# rs485.net
KiCad netlist of a schematic drawn in Altium Designer
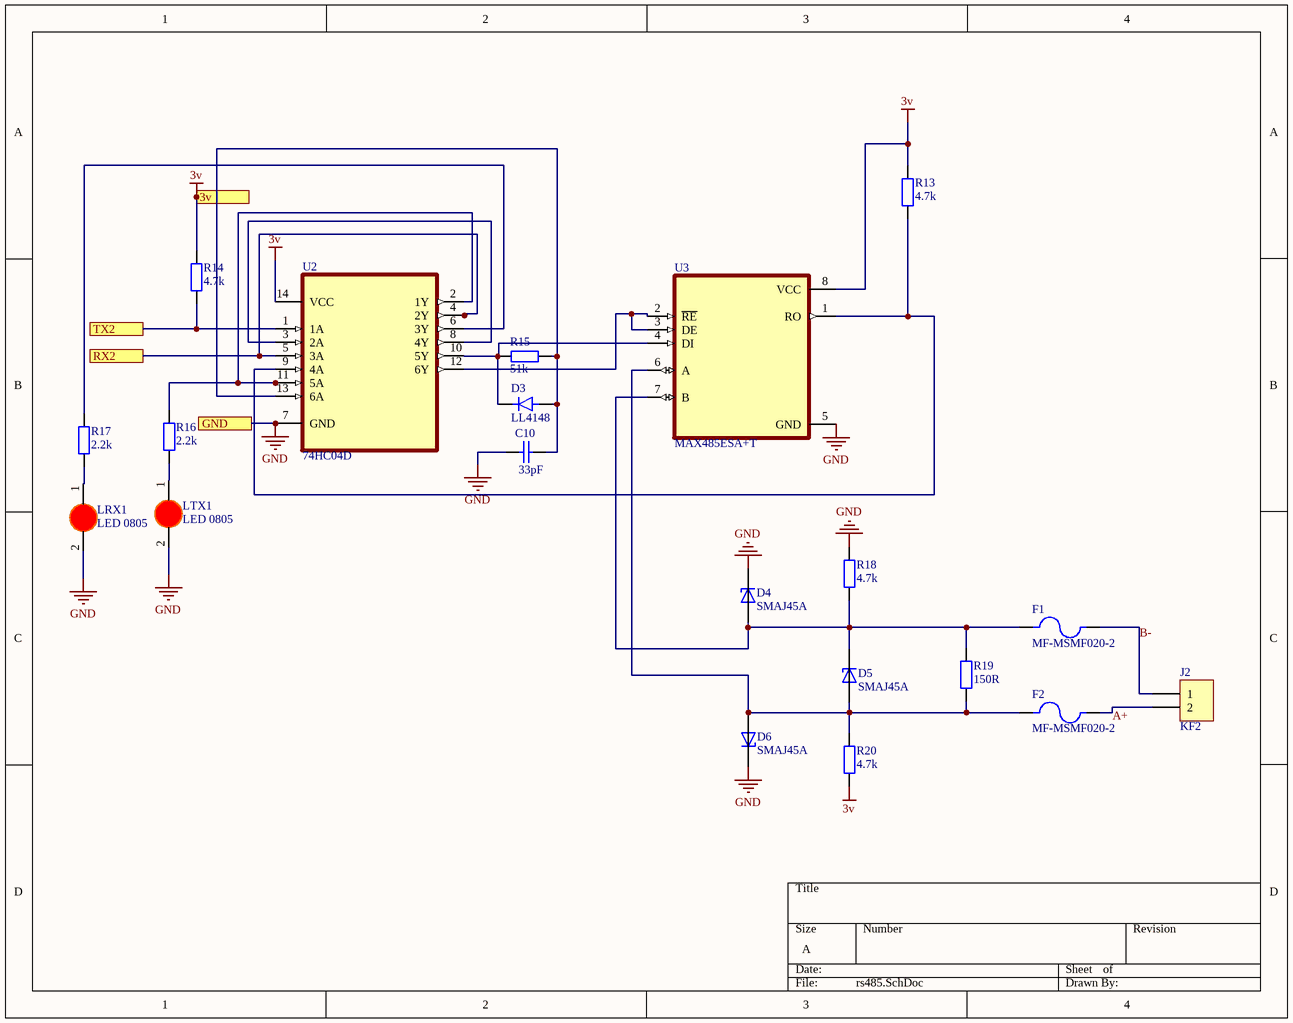
[diagram p0: rs485.SchDoc]

(export (version "E")
  (design (tool "Eeschema 10.0.6"))
  (components
    (comp (ref "C10")
      (value "33pF")
      (footprint "tu 0805")
      (description "Dán")
      (libsource (lib "Altium_Lib_by_KhueNguyenCreator") (part "Tu 0805 33pF 50V 10%"))
    )
    (comp (ref "D3")
      (value "LL4148")
      (footprint "DIO_LL4148")
      (description "Diode Small Signal Switching 100V 0.15A Automotive 2-Pin Mini-MELF T/R")
      (fields (field (name "MF") "Diotec Semiconductor"))
      (libsource (lib "LinhKienDoAn") (part "LL4148"))
    )
    (comp (ref "D4")
      (value "SMAJ45A")
      (footprint "DIOM4325X250N")
      (description "72.7V Clamp 5.5A Ipp Tvs Diode Surface Mount DO-214AC (SMA)")
      (fields (field (name "MF") "Littelfuse"))
      (libsource (lib "LinhKienDoAn") (part "SMAJ45A"))
    )
    (comp (ref "D5")
      (value "SMAJ45A")
      (footprint "DIOM4325X250N")
      (description "72.7V Clamp 5.5A Ipp Tvs Diode Surface Mount DO-214AC (SMA)")
      (fields (field (name "MF") "Littelfuse"))
      (libsource (lib "LinhKienDoAn") (part "SMAJ45A"))
    )
    (comp (ref "D6")
      (value "SMAJ45A")
      (footprint "DIOM4325X250N")
      (description "72.7V Clamp 5.5A Ipp Tvs Diode Surface Mount DO-214AC (SMA)")
      (fields (field (name "MF") "Littelfuse"))
      (libsource (lib "LinhKienDoAn") (part "SMAJ45A"))
    )
    (comp (ref "F1")
      (value "MF-MSMF020-2")
      (footprint "FUSER_MF-MSMF020-2")
      (description "Polymeric PTC Resettable Fuse 30V 200 mA Ih Surface Mount 1812 (4532 Metric), Concave")
      (fields (field (name "MF") "Bourns"))
      (libsource (lib "LinhKienDoAn") (part "MF-MSMF020-2"))
    )
    (comp (ref "F2")
      (value "MF-MSMF020-2")
      (footprint "FUSER_MF-MSMF020-2")
      (description "Polymeric PTC Resettable Fuse 30V 200 mA Ih Surface Mount 1812 (4532 Metric), Concave")
      (fields (field (name "MF") "Bourns"))
      (libsource (lib "LinhKienDoAn") (part "MF-MSMF020-2"))
    )
    (comp (ref "J2")
      (value "KF2")
      (footprint "KF2-3.5")
      (fields
        (field (name "MANUFACTURER") "Würth Elektronik eiSos GmbH")
        (field (name "PARTNO") "691103110002")
        (field (name "CREATED BY") "Karrer Zheng")
      )
      (libsource (lib "LIBRARY1") (part "KF2"))
    )
    (comp (ref "LRX1")
      (value "LED 0805")
      (footprint "LED-0805-Red")
      (description "Dán")
      (libsource (lib "Altium_Lib_by_KhueNguyenCreator") (part "LED 0805 Do"))
    )
    (comp (ref "LTX1")
      (value "LED 0805")
      (footprint "LED-0805-Red")
      (description "Dán")
      (libsource (lib "Altium_Lib_by_KhueNguyenCreator") (part "LED 0805 Do"))
    )
    (comp (ref "R13")
      (value "4.7k")
      (footprint "tro smd 0603")
      (description "Dán")
      (libsource (lib "Altium_Lib_by_KhueNguyenCreator") (part "Tro 0603 5% 4.7k"))
    )
    (comp (ref "R14")
      (value "4.7k")
      (footprint "tro smd 0603")
      (description "Dán")
      (libsource (lib "Altium_Lib_by_KhueNguyenCreator") (part "Tro 0603 5% 4.7k"))
    )
    (comp (ref "R15")
      (value "51k")
      (footprint "tro smd 0603")
      (description "Dán")
      (libsource (lib "Altium_Lib_by_KhueNguyenCreator") (part "Tro 0603 5% 51k"))
    )
    (comp (ref "R16")
      (value "2.2k")
      (footprint "tro smd 0603")
      (description "Dán")
      (libsource (lib "Altium_Lib_by_KhueNguyenCreator") (part "Tro 0603 5% 2.2k"))
    )
    (comp (ref "R17")
      (value "2.2k")
      (footprint "tro smd 0603")
      (description "Dán")
      (libsource (lib "Altium_Lib_by_KhueNguyenCreator") (part "Tro 0603 5% 2.2k"))
    )
    (comp (ref "R18")
      (value "4.7k")
      (footprint "tro smd 0603")
      (description "Dán")
      (libsource (lib "Altium_Lib_by_KhueNguyenCreator") (part "Tro 0603 5% 4.7k"))
    )
    (comp (ref "R19")
      (value "150R")
      (footprint "tro smd 0603")
      (description "Dán")
      (libsource (lib "Altium_Lib_by_KhueNguyenCreator") (part "Tro 0603 5% 150R"))
    )
    (comp (ref "R20")
      (value "4.7k")
      (footprint "tro smd 0603")
      (description "Dán")
      (libsource (lib "Altium_Lib_by_KhueNguyenCreator") (part "Tro 0603 5% 4.7k"))
    )
    (comp (ref "U2")
      (value "74HC04D")
      (footprint "SOIC127P600X175-14N")
      (description "Inverter IC 6 Channel 14-SOIC")
      (fields (field (name "MF") "Toshiba"))
      (libsource (lib "LinhKienDoAn") (part "74HC04D"))
    )
    (comp (ref "U3")
      (value "MAX485ESA+T")
      (footprint "SOIC127P600X175-8N")
      (description "1/1 Transceiver Half RS422, RS485 8-SOIC")
      (fields (field (name "MP") "MAX485ESA") (field (name "MF") "Maxim Integrated"))
      (libsource (lib "MAX485ESA_T") (part "MAX485ESA+T"))
    )
  )
  (nets
    (net (code "1") (name "/A+") (class "Default")
      (node (ref "F2") (pin "2") (pinfunction "2_2") (pintype "passive"))
      (node (ref "J2") (pin "2") (pinfunction "2_2") (pintype "passive"))
    )
    (net (code "2") (name "/B-") (class "Default")
      (node (ref "F1") (pin "2") (pinfunction "2_2") (pintype "passive"))
      (node (ref "J2") (pin "1") (pinfunction "1_1") (pintype "passive"))
    )
    (net (code "3") (name "/RX2") (class "Default")
      (node (ref "U2") (pin "4") (pinfunction "2Y_4") (pintype "output"))
      (node (ref "U2") (pin "5") (pinfunction "3A_5") (pintype "input"))
    )
    (net (code "4") (name "/TX2") (class "Default")
      (node (ref "R14") (pin "1") (pinfunction "1_1") (pintype "passive"))
      (node (ref "U2") (pin "1") (pinfunction "1A_1") (pintype "input"))
    )
    (net (code "5") (name "3v") (class "Default")
      (node (ref "R13") (pin "2") (pinfunction "2_2") (pintype "passive"))
      (node (ref "R14") (pin "2") (pinfunction "2_2") (pintype "passive"))
      (node (ref "R20") (pin "1") (pinfunction "1_1") (pintype "passive"))
      (node (ref "U2") (pin "14") (pinfunction "VCC_14") (pintype "power_in"))
      (node (ref "U3") (pin "8") (pinfunction "VCC_8") (pintype "power_in"))
    )
    (net (code "6") (name "GND") (class "Default")
      (node (ref "C10") (pin "2") (pinfunction "2_2") (pintype "passive"))
      (node (ref "D4") (pin "C") (pinfunction "C_C") (pintype "passive"))
      (node (ref "D6") (pin "C") (pinfunction "C_C") (pintype "passive"))
      (node (ref "LRX1") (pin "2") (pinfunction "K_2") (pintype "passive"))
      (node (ref "LTX1") (pin "2") (pinfunction "K_2") (pintype "passive"))
      (node (ref "R18") (pin "2") (pinfunction "2_2") (pintype "passive"))
      (node (ref "U2") (pin "7") (pinfunction "GND_7") (pintype "passive"))
      (node (ref "U3") (pin "5") (pinfunction "GND_5") (pintype "power_in"))
    )
    (net (code "7") (name "Net-(LRX1-A)") (class "Default")
      (node (ref "LRX1") (pin "1") (pinfunction "A_1") (pintype "passive"))
      (node (ref "R17") (pin "1") (pinfunction "1_1") (pintype "passive"))
    )
    (net (code "8") (name "Net-(LTX1-A)") (class "Default")
      (node (ref "LTX1") (pin "1") (pinfunction "A_1") (pintype "passive"))
      (node (ref "R16") (pin "1") (pinfunction "1_1") (pintype "passive"))
    )
    (net (code "9") (name "Net-(U2-1Y)") (class "Default")
      (node (ref "R16") (pin "2") (pinfunction "2_2") (pintype "passive"))
      (node (ref "U2") (pin "11") (pinfunction "5A_11") (pintype "input"))
      (node (ref "U2") (pin "2") (pinfunction "1Y_2") (pintype "output"))
    )
    (net (code "10") (name "Net-(U2-2A)") (class "Default")
      (node (ref "U2") (pin "3") (pinfunction "2A_3") (pintype "input"))
      (node (ref "U2") (pin "8") (pinfunction "4Y_8") (pintype "output"))
    )
    (net (code "11") (name "Net-(U2-3Y)") (class "Default")
      (node (ref "R17") (pin "2") (pinfunction "2_2") (pintype "passive"))
      (node (ref "U2") (pin "6") (pinfunction "3Y_6") (pintype "output"))
    )
    (net (code "12") (name "Net-(U2-4A)") (class "Default")
      (node (ref "R13") (pin "1") (pinfunction "1_1") (pintype "passive"))
      (node (ref "U2") (pin "9") (pinfunction "4A_9") (pintype "input"))
      (node (ref "U3") (pin "1") (pinfunction "RO_1") (pintype "output"))
    )
    (net (code "13") (name "Net-(U2-5Y)") (class "Default")
      (node (ref "D3") (pin "C") (pinfunction "C_C") (pintype "passive"))
      (node (ref "R15") (pin "1") (pinfunction "1_1") (pintype "passive"))
      (node (ref "U2") (pin "10") (pinfunction "5Y_10") (pintype "output"))
      (node (ref "U3") (pin "4") (pinfunction "DI_4") (pintype "input"))
    )
    (net (code "14") (name "Net-(U2-6A)") (class "Default")
      (node (ref "C10") (pin "1") (pinfunction "1_1") (pintype "passive"))
      (node (ref "D3") (pin "A") (pinfunction "A_A") (pintype "passive"))
      (node (ref "R15") (pin "2") (pinfunction "2_2") (pintype "passive"))
      (node (ref "U2") (pin "13") (pinfunction "6A_13") (pintype "input"))
    )
    (net (code "15") (name "Net-(U2-6Y)") (class "Default")
      (node (ref "U2") (pin "12") (pinfunction "6Y_12") (pintype "output"))
      (node (ref "U3") (pin "2") (pinfunction "~{RE}_2") (pintype "input"))
      (node (ref "U3") (pin "3") (pinfunction "DE_3") (pintype "input"))
    )
    (net (code "16") (name "Net-(U3-A)") (class "Default")
      (node (ref "D5") (pin "A") (pinfunction "A_A") (pintype "passive"))
      (node (ref "D6") (pin "A") (pinfunction "A_A") (pintype "passive"))
      (node (ref "F2") (pin "1") (pinfunction "1_1") (pintype "passive"))
      (node (ref "R19") (pin "1") (pinfunction "1_1") (pintype "passive"))
      (node (ref "R20") (pin "2") (pinfunction "2_2") (pintype "passive"))
      (node (ref "U3") (pin "6") (pinfunction "A_6") (pintype "bidirectional"))
    )
    (net (code "17") (name "Net-(U3-B)") (class "Default")
      (node (ref "D4") (pin "A") (pinfunction "A_A") (pintype "passive"))
      (node (ref "D5") (pin "C") (pinfunction "C_C") (pintype "passive"))
      (node (ref "F1") (pin "1") (pinfunction "1_1") (pintype "passive"))
      (node (ref "R18") (pin "1") (pinfunction "1_1") (pintype "passive"))
      (node (ref "R19") (pin "2") (pinfunction "2_2") (pintype "passive"))
      (node (ref "U3") (pin "7") (pinfunction "B_7") (pintype "bidirectional"))
    )
  )
)
